# X4.net
KiCad netlist of a schematic drawn in Altium Designer
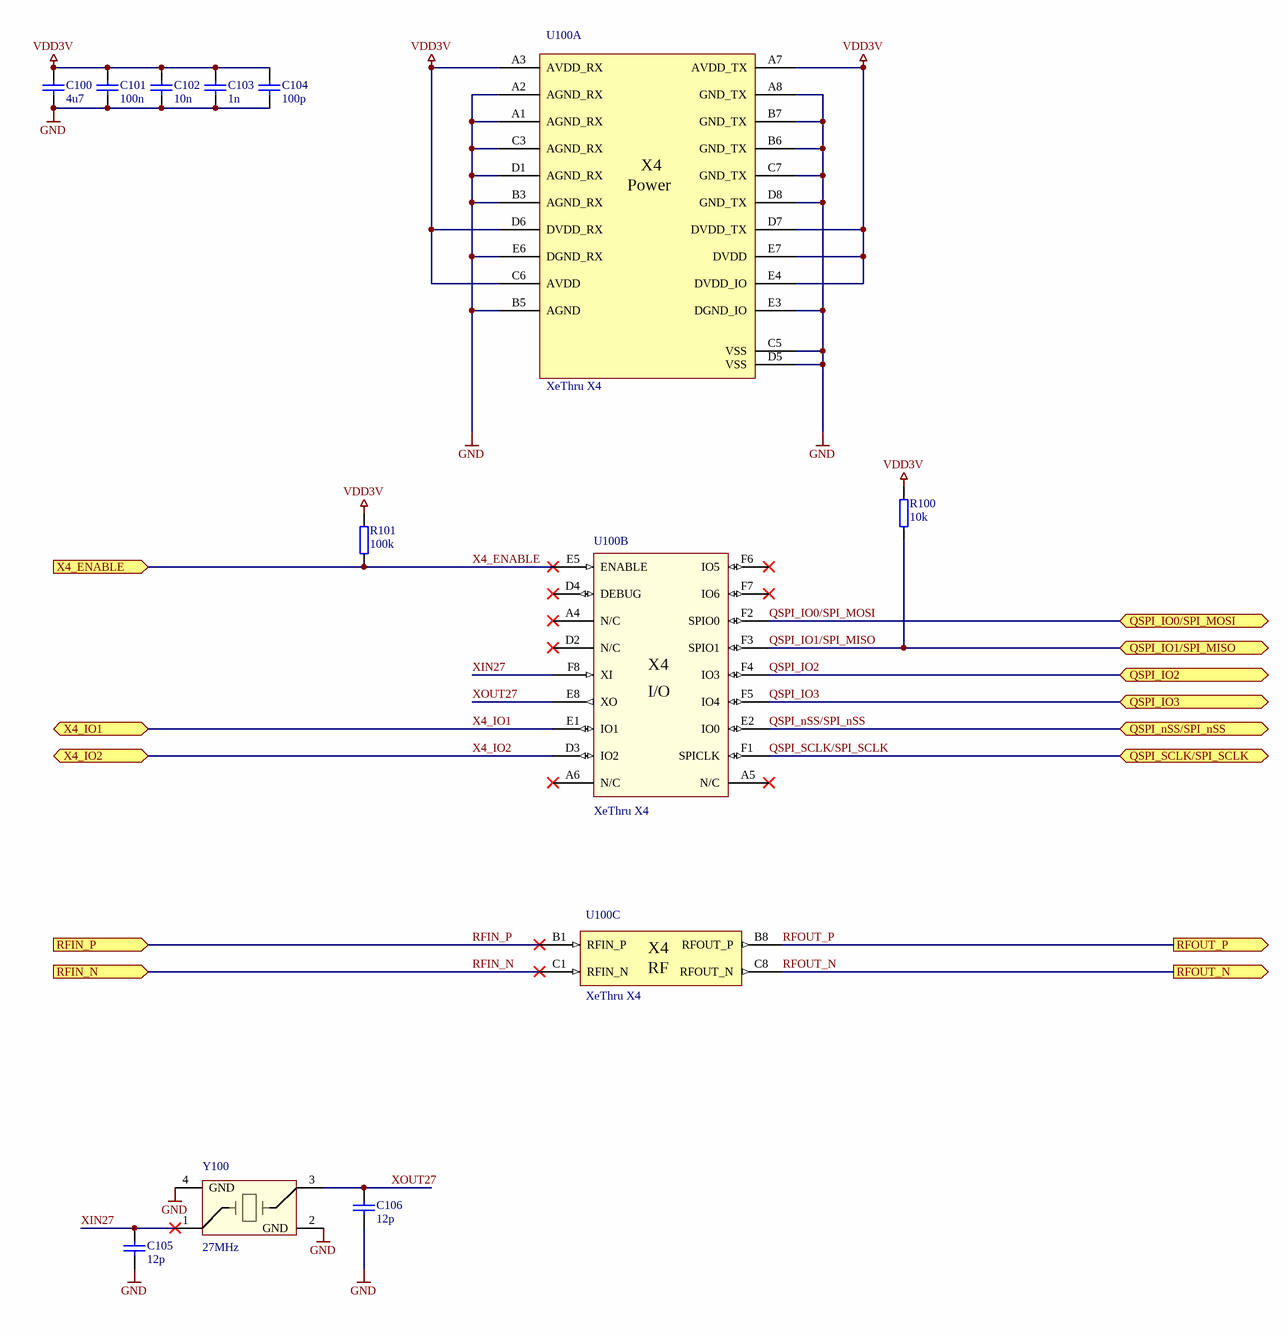
[diagram p0: X4.SchDoc]

(export (version "E")
  (design (tool "Eeschema 10.0.6"))
  (components
    (comp (ref "C100")
      (value "4u7")
      (footprint "0603-CAPACITOR-NONPOL")
      (description "CAPACITOR, 4u7, 0603, 10%, 10V, X5R")
      (fields (field (name "MANUFACTURER") "--"))
      (libsource (lib "novelda_altiumlib") (part "CAPACITOR-NONPOL"))
    )
    (comp (ref "C101")
      (value "100n")
      (footprint "0402-CAPACITOR-NONPOL")
      (description "CAPACITOR, 100n, 0402, 10%, 10V, X5R")
      (fields (field (name "MANUFACTURER") "--"))
      (libsource (lib "novelda_altiumlib") (part "CAPACITOR-NONPOL"))
    )
    (comp (ref "C102")
      (value "10n")
      (footprint "0402-CAPACITOR-NONPOL")
      (description "CAPACITOR, 10n, 0402, 10%, 25V, X7R")
      (fields (field (name "MANUFACTURER") "--"))
      (libsource (lib "novelda_altiumlib") (part "CAPACITOR-NONPOL"))
    )
    (comp (ref "C103")
      (value "1n")
      (footprint "0402-CAPACITOR-NONPOL")
      (description "CAPACITOR, 1n, 0402, 10%, 25V, X7R")
      (fields (field (name "MANUFACTURER") "--"))
      (libsource (lib "novelda_altiumlib") (part "CAPACITOR-NONPOL"))
    )
    (comp (ref "C104")
      (value "100p")
      (footprint "0402-CAPACITOR-NONPOL")
      (description "CAPACITOR, 100p, 0402, 20%, 50V, X7R")
      (fields (field (name "MANUFACTURER") "--"))
      (libsource (lib "novelda_altiumlib") (part "CAPACITOR-NONPOL"))
    )
    (comp (ref "C105")
      (value "12p")
      (footprint "0402-CAPACITOR-NONPOL")
      (description "CAPACITOR, 12p, 0402, 5%, 50V, NP0")
      (fields (field (name "MANUFACTURER") "--"))
      (libsource (lib "novelda_altiumlib") (part "CAPACITOR-NONPOL"))
    )
    (comp (ref "C106")
      (value "12p")
      (footprint "0402-CAPACITOR-NONPOL")
      (description "CAPACITOR, 12p, 0402, 5%, 50V, NP0")
      (fields (field (name "MANUFACTURER") "--"))
      (libsource (lib "novelda_altiumlib") (part "CAPACITOR-NONPOL"))
    )
    (comp (ref "R100")
      (value "10k")
      (footprint "0402-RESISTOR")
      (description "RESISTOR, 10k, 0402, 1%, 63mW")
      (fields (field (name "MANUFACTURER") "--"))
      (libsource (lib "novelda_altiumlib") (part "RESISTOR"))
    )
    (comp (ref "R101")
      (value "100k")
      (footprint "0402-RESISTOR")
      (description "RESISTOR, 100k, 0402, 1%, 63mW")
      (fields (field (name "MANUFACTURER") "--"))
      (libsource (lib "novelda_altiumlib") (part "RESISTOR"))
    )
    (comp (ref "U100")
      (value "XeThru X4")
      (footprint "200106-002")
      (fields (field (name "MANUFACTURER") "Novelda") (field (name "MPN") "200260-002"))
      (libsource (lib "novelda_altiumlib") (part "200260-002"))
    )
    (comp (ref "Y100")
      (value "27MHz")
      (footprint "200281")
      (description "LFXTAL072115, CRYSTAL 27MHZ, 10PF, SMD")
      (fields (field (name "MANUFACTURER") "IQD Frequency Products") (field (name "MPN") "LFXTAL072115"))
      (libsource (lib "novelda_altiumlib") (part "200281"))
    )
  )
  (nets
    (net (code "1") (name "/QSPI_IO0{slash}SPI_MOSI") (class "Default")
      (node (ref "U100") (pin "F2") (pinfunction "SPIO0_F2") (pintype "bidirectional"))
    )
    (net (code "2") (name "/QSPI_IO1{slash}SPI_MISO") (class "Default")
      (node (ref "R100") (pin "1") (pinfunction "1_1") (pintype "passive"))
      (node (ref "U100") (pin "F3") (pinfunction "SPIO1_F3") (pintype "bidirectional"))
    )
    (net (code "3") (name "/QSPI_IO2") (class "Default")
      (node (ref "U100") (pin "F4") (pinfunction "IO3_F4") (pintype "bidirectional"))
    )
    (net (code "4") (name "/QSPI_IO3") (class "Default")
      (node (ref "U100") (pin "F5") (pinfunction "IO4_F5") (pintype "bidirectional"))
    )
    (net (code "5") (name "/QSPI_SCLK{slash}SPI_SCLK") (class "Default")
      (node (ref "U100") (pin "F1") (pinfunction "SPICLK_F1") (pintype "bidirectional"))
    )
    (net (code "6") (name "/QSPI_nSS{slash}SPI_nSS") (class "Default")
      (node (ref "U100") (pin "E2") (pinfunction "IO0_E2") (pintype "bidirectional"))
    )
    (net (code "7") (name "/RFIN_N") (class "Default")
      (node (ref "U100") (pin "C1") (pinfunction "RFIN_N_C1") (pintype "input+no_connect"))
    )
    (net (code "8") (name "/RFIN_P") (class "Default")
      (node (ref "U100") (pin "B1") (pinfunction "RFIN_P_B1") (pintype "input+no_connect"))
    )
    (net (code "9") (name "/RFOUT_N") (class "Default")
      (node (ref "U100") (pin "C8") (pinfunction "RFOUT_N_C8") (pintype "output"))
    )
    (net (code "10") (name "/RFOUT_P") (class "Default")
      (node (ref "U100") (pin "B8") (pinfunction "RFOUT_P_B8") (pintype "output"))
    )
    (net (code "11") (name "/X4_ENABLE") (class "Default")
      (node (ref "R101") (pin "1") (pinfunction "1_1") (pintype "passive"))
      (node (ref "U100") (pin "E5") (pinfunction "ENABLE_E5") (pintype "input"))
    )
    (net (code "12") (name "/X4_IO1") (class "Default")
      (node (ref "U100") (pin "E1") (pinfunction "IO1_E1") (pintype "bidirectional"))
    )
    (net (code "13") (name "/X4_IO2") (class "Default")
      (node (ref "U100") (pin "D3") (pinfunction "IO2_D3") (pintype "bidirectional"))
    )
    (net (code "14") (name "/XIN27") (class "Default")
      (node (ref "C105") (pin "1") (pinfunction "1_1") (pintype "passive"))
      (node (ref "U100") (pin "F8") (pinfunction "XI_F8") (pintype "input"))
      (node (ref "Y100") (pin "1") (pinfunction "1_1") (pintype "passive"))
    )
    (net (code "15") (name "/XOUT27") (class "Default")
      (node (ref "C106") (pin "1") (pinfunction "1_1") (pintype "passive"))
      (node (ref "U100") (pin "E8") (pinfunction "XO_E8") (pintype "output"))
      (node (ref "Y100") (pin "3") (pinfunction "3_3") (pintype "passive"))
    )
    (net (code "16") (name "GND") (class "Default")
      (node (ref "C100") (pin "2") (pinfunction "2_2") (pintype "passive"))
      (node (ref "C101") (pin "2") (pinfunction "2_2") (pintype "passive"))
      (node (ref "C102") (pin "2") (pinfunction "2_2") (pintype "passive"))
      (node (ref "C103") (pin "2") (pinfunction "2_2") (pintype "passive"))
      (node (ref "C104") (pin "2") (pinfunction "2_2") (pintype "passive"))
      (node (ref "C105") (pin "2") (pinfunction "2_2") (pintype "passive"))
      (node (ref "C106") (pin "2") (pinfunction "2_2") (pintype "passive"))
      (node (ref "U100") (pin "A1") (pinfunction "AGND_RX_A1") (pintype "power_in"))
      (node (ref "U100") (pin "A2") (pinfunction "AGND_RX_A2") (pintype "power_in"))
      (node (ref "U100") (pin "A8") (pinfunction "GND_TX_A8") (pintype "power_in"))
      (node (ref "U100") (pin "B3") (pinfunction "AGND_RX_B3") (pintype "power_in"))
      (node (ref "U100") (pin "B5") (pinfunction "AGND_B5") (pintype "power_in"))
      (node (ref "U100") (pin "B6") (pinfunction "GND_TX_B6") (pintype "power_in"))
      (node (ref "U100") (pin "B7") (pinfunction "GND_TX_B7") (pintype "power_in"))
      (node (ref "U100") (pin "C3") (pinfunction "AGND_RX_C3") (pintype "power_in"))
      (node (ref "U100") (pin "C5") (pinfunction "VSS_C5") (pintype "power_in"))
      (node (ref "U100") (pin "C7") (pinfunction "GND_TX_C7") (pintype "power_in"))
      (node (ref "U100") (pin "D1") (pinfunction "AGND_RX_D1") (pintype "power_in"))
      (node (ref "U100") (pin "D5") (pinfunction "VSS_D5") (pintype "power_in"))
      (node (ref "U100") (pin "D8") (pinfunction "GND_TX_D8") (pintype "power_in"))
      (node (ref "U100") (pin "E3") (pinfunction "DGND_IO_E3") (pintype "power_in"))
      (node (ref "U100") (pin "E6") (pinfunction "DGND_RX_E6") (pintype "power_in"))
      (node (ref "Y100") (pin "2") (pinfunction "GND_2") (pintype "passive"))
      (node (ref "Y100") (pin "4") (pinfunction "GND_4") (pintype "passive"))
    )
    (net (code "17") (name "VDD3V") (class "Default")
      (node (ref "C100") (pin "1") (pinfunction "1_1") (pintype "passive"))
      (node (ref "C101") (pin "1") (pinfunction "1_1") (pintype "passive"))
      (node (ref "C102") (pin "1") (pinfunction "1_1") (pintype "passive"))
      (node (ref "C103") (pin "1") (pinfunction "1_1") (pintype "passive"))
      (node (ref "C104") (pin "1") (pinfunction "1_1") (pintype "passive"))
      (node (ref "R100") (pin "2") (pinfunction "2_2") (pintype "passive"))
      (node (ref "R101") (pin "2") (pinfunction "2_2") (pintype "passive"))
      (node (ref "U100") (pin "A3") (pinfunction "AVDD_RX_A3") (pintype "power_in"))
      (node (ref "U100") (pin "A7") (pinfunction "AVDD_TX_A7") (pintype "power_in"))
      (node (ref "U100") (pin "C6") (pinfunction "AVDD_C6") (pintype "power_in"))
      (node (ref "U100") (pin "D6") (pinfunction "DVDD_RX_D6") (pintype "power_in"))
      (node (ref "U100") (pin "D7") (pinfunction "DVDD_TX_D7") (pintype "power_in"))
      (node (ref "U100") (pin "E4") (pinfunction "DVDD_IO_E4") (pintype "power_in"))
      (node (ref "U100") (pin "E7") (pinfunction "DVDD_E7") (pintype "power_in"))
    )
    (net (code "18") (name "unconnected-(U100B-DEBUG-PadD4)") (class "Default")
      (node (ref "U100") (pin "D4") (pinfunction "DEBUG_D4") (pintype "bidirectional+no_connect"))
    )
    (net (code "19") (name "unconnected-(U100B-IO5-PadF6)") (class "Default")
      (node (ref "U100") (pin "F6") (pinfunction "IO5_F6") (pintype "bidirectional+no_connect"))
    )
    (net (code "20") (name "unconnected-(U100B-IO6-PadF7)") (class "Default")
      (node (ref "U100") (pin "F7") (pinfunction "IO6_F7") (pintype "bidirectional+no_connect"))
    )
    (net (code "21") (name "unconnected-(U100B-N{slash}C-PadA4)") (class "Default")
      (node (ref "U100") (pin "A4") (pinfunction "N/C_A4") (pintype "passive+no_connect"))
    )
    (net (code "22") (name "unconnected-(U100B-N{slash}C-PadA5)") (class "Default")
      (node (ref "U100") (pin "A5") (pinfunction "N/C_A5") (pintype "passive+no_connect"))
    )
    (net (code "23") (name "unconnected-(U100B-N{slash}C-PadA6)") (class "Default")
      (node (ref "U100") (pin "A6") (pinfunction "N/C_A6") (pintype "passive+no_connect"))
    )
    (net (code "24") (name "unconnected-(U100B-N{slash}C-PadD2)") (class "Default")
      (node (ref "U100") (pin "D2") (pinfunction "N/C_D2") (pintype "passive+no_connect"))
    )
  )
)
